# AL1_Signal_Isolation.net
KiCad netlist of a schematic drawn in Altium Designer
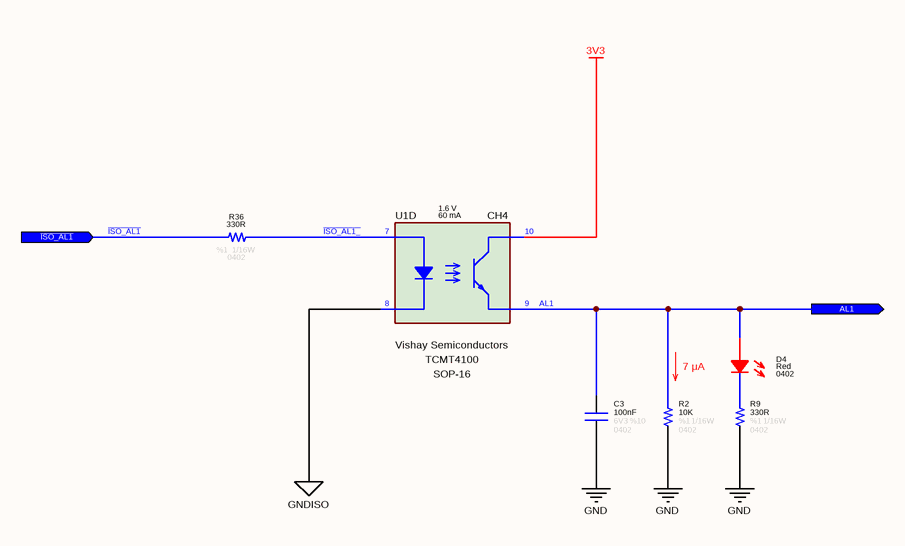
[diagram p0: AL1 Signal Isolation.SchDoc]

(export (version "E")
  (design (tool "Eeschema 10.0.6"))
  (components
    (comp (ref "C3")
      (value "100nF")
      (footprint "CAPACITOR_0402")
      (description "Capacitor - 100nF [0402-6V3] (Ceramic)")
      (fields
        (field (name "MANUFACTURER PART NUMBER") "04026D104KAT4A")
        (field (name "TOLERANCE") "%10")
        (field (name "VOLTAGE") "6V3")
        (field (name "CASE") "0402")
        (field (name "Comment") "Capacitor - 100nF [0402] (Ceramic)")
      )
      (libsource (lib "Akkoyun") (part "Capacitor - 100nF [0402-6V3]"))
    )
    (comp (ref "D4")
      (value "SMD LED (Red)")
      (footprint "LED_0402")
      (description "Standard LEDs - SMD MINI-MOLD ULTRA COMPACT RED")
      (fields
        (field (name "MANUFACTURER PART NUMBER") "SML-P12VTT86R")
        (field (name "CASE") "0402")
        (field (name "COLOR") "Red")
      )
      (libsource (lib "Akkoyun") (part "Diode - LED (0402-Red)"))
    )
    (comp (ref "R2")
      (value "10K")
      (footprint "RESISTOR_0402")
      (description "Thick Film Resistors - SMD 1/16 W 10 KOhm 1%")
      (fields
        (field (name "MANUFACTURER PART NUMBER") "CRCW040210K0FKED")
        (field (name "TOLERANCE") "%1")
        (field (name "CASE") "0402")
        (field (name "POWER") "1/16W")
        (field (name "Comment") "10K - 0402 - %1 - 1/16W")
      )
      (libsource (lib "Akkoyun") (part "Resistor - 10K [0402]"))
    )
    (comp (ref "R9")
      (value "330R")
      (footprint "RESISTOR_0402")
      (description "Thick Film Resistors - SMD 1/16 W 330 Ohm 1%")
      (fields
        (field (name "MANUFACTURER PART NUMBER") "CRCW0402330RFKED")
        (field (name "CASE") "0402")
        (field (name "TOLERANCE") "%1")
        (field (name "POWER") "1/16W")
        (field (name "Comment") "330R - 0402 - %1 - 1/16W")
      )
      (libsource (lib "Akkoyun") (part "Resistor - 330R [0402]"))
    )
    (comp (ref "R36")
      (value "330R")
      (footprint "RESISTOR_0402")
      (description "Thick Film Resistors - SMD 1/16 W 330 Ohm 1%")
      (fields
        (field (name "MANUFACTURER PART NUMBER") "CRCW0402330RFKED")
        (field (name "CASE") "0402")
        (field (name "TOLERANCE") "%1")
        (field (name "POWER") "1/16W")
        (field (name "Comment") "330R - 0402 - %1 - 1/16W")
      )
      (libsource (lib "Akkoyun") (part "Resistor - 330R [0402]"))
    )
    (comp (ref "U1")
      (value "TCMT4100")
      (footprint "SO-16")
      (description "OptpCoupler 4CH 16 Pin (SOP16)")
      (fields
        (field (name "IF - FORWARD CURRENT") "60 mA")
        (field (name "VF - FORWARD VOLTAGE") "1.6 V")
        (field (name "MANUFACTURER NAME") "Vishay Semiconductors")
        (field (name "MANUFACTURER PART NUMBER") "TCMT4100")
        (field (name "CASE") "SOP-16")
      )
      (libsource (lib "Akkoyun") (part "IC - TCMT4100"))
    )
  )
  (nets
    (net (code "1") (name "/AL1") (class "Default")
      (node (ref "C3") (pin "2") (pinfunction "2_2") (pintype "passive"))
      (node (ref "D4") (pin "2") (pinfunction "2_2") (pintype "passive"))
      (node (ref "R2") (pin "2") (pinfunction "2_2") (pintype "passive"))
      (node (ref "U1") (pin "9") (pinfunction "Emiter_CH4_9") (pintype "open_emitter"))
    )
    (net (code "2") (name "/~{ISO_AL1_}") (class "Default")
      (node (ref "R36") (pin "1") (pinfunction "1_1") (pintype "passive"))
      (node (ref "U1") (pin "7") (pinfunction "Anode_CH4_7") (pintype "passive"))
    )
    (net (code "3") (name "/~{ISO_AL1}") (class "Default")
      (node (ref "R36") (pin "2") (pinfunction "2_2") (pintype "passive"))
    )
    (net (code "4") (name "3V3") (class "Default")
      (node (ref "U1") (pin "10") (pinfunction "Collector_CH4_10") (pintype "passive"))
    )
    (net (code "5") (name "GND") (class "Default")
      (node (ref "C3") (pin "1") (pinfunction "1_1") (pintype "passive"))
      (node (ref "R2") (pin "1") (pinfunction "1_1") (pintype "passive"))
      (node (ref "R9") (pin "1") (pinfunction "1_1") (pintype "passive"))
    )
    (net (code "6") (name "GNDISO") (class "Default")
      (node (ref "U1") (pin "8") (pinfunction "Cathode_CH4_8") (pintype "passive"))
    )
    (net (code "7") (name "Net-(D4-Pad1)") (class "Default")
      (node (ref "D4") (pin "1") (pinfunction "1_1") (pintype "passive"))
      (node (ref "R9") (pin "2") (pinfunction "2_2") (pintype "passive"))
    )
  )
)
